# ADS8686S_BLOCK_B.net
KiCad netlist of a schematic drawn in Altium Designer
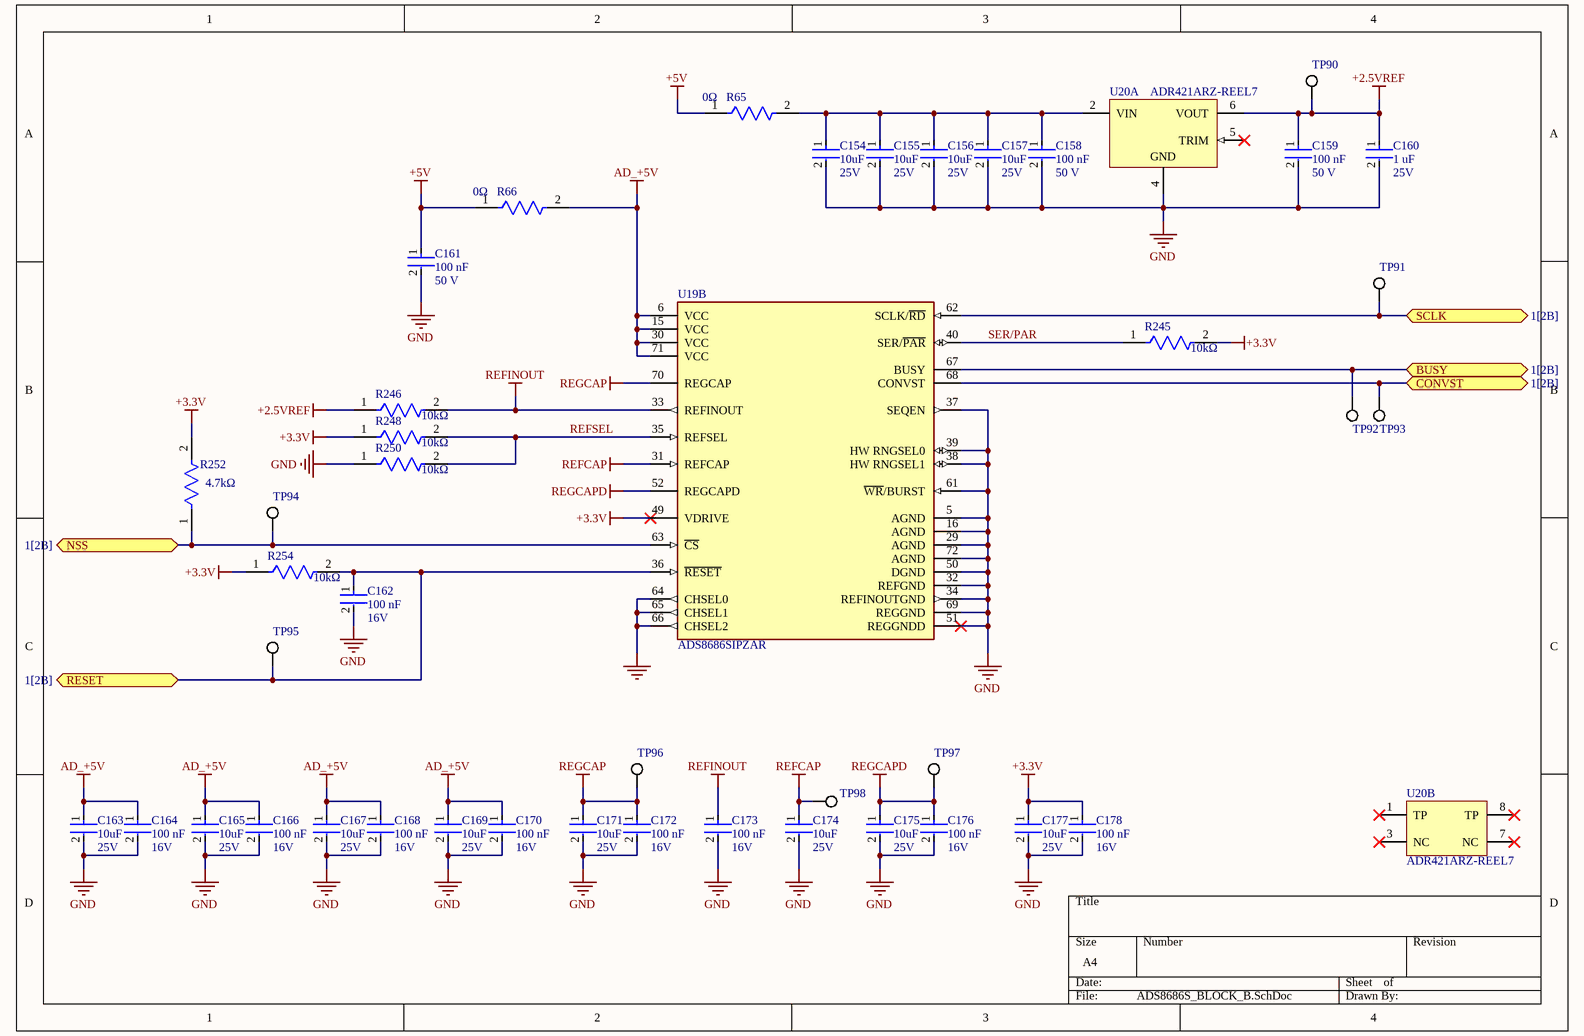
[diagram p0: ADS8686S_BLOCK_B.SchDoc]

(export (version "E")
  (design (tool "Eeschema 10.0.6"))
  (components
    (comp (ref "C154")
      (value "C1608X5R1E106M080AC")
      (footprint "FP-C1608-080-IPC_B")
      (description "CAP CER 10UF 25V X5R 0603")
      (fields
        (field (name "VOLTAGE RATING") "25V")
        (field (name "TOLERANCE") "20%")
        (field (name "CAPACITANCE") "10uF")
      )
      (libsource (lib "Altium Content Vault") (part "11868f565c42a9108669ba33697ecf6"))
    )
    (comp (ref "C155")
      (value "C1608X5R1E106M080AC")
      (footprint "FP-C1608-080-IPC_B")
      (description "CAP CER 10UF 25V X5R 0603")
      (fields
        (field (name "VOLTAGE RATING") "25V")
        (field (name "TOLERANCE") "20%")
        (field (name "CAPACITANCE") "10uF")
      )
      (libsource (lib "Altium Content Vault") (part "11868f565c42a9108669ba33697ecf6"))
    )
    (comp (ref "C156")
      (value "C1608X5R1E106M080AC")
      (footprint "FP-C1608-080-IPC_B")
      (description "CAP CER 10UF 25V X5R 0603")
      (fields
        (field (name "VOLTAGE RATING") "25V")
        (field (name "TOLERANCE") "20%")
        (field (name "CAPACITANCE") "10uF")
      )
      (libsource (lib "Altium Content Vault") (part "11868f565c42a9108669ba33697ecf6"))
    )
    (comp (ref "C157")
      (value "C1608X5R1E106M080AC")
      (footprint "FP-C1608-080-IPC_B")
      (description "CAP CER 10UF 25V X5R 0603")
      (fields
        (field (name "VOLTAGE RATING") "25V")
        (field (name "TOLERANCE") "20%")
        (field (name "CAPACITANCE") "10uF")
      )
      (libsource (lib "Altium Content Vault") (part "11868f565c42a9108669ba33697ecf6"))
    )
    (comp (ref "C158")
      (value "100 nF")
      (footprint "FP-C0603C-CF-IPC_B")
      (description "CAP CER 0.1UF 50V 20% X7R 0603")
      (fields
        (field (name "VOLTAGE RATING") "50 V")
        (field (name "MANUFACTURER PART NUMBER") "C0603C104M5RACTU")
        (field (name "MANUFACTURER") "KEMET")
      )
      (libsource (lib "Altium Content Vault") (part "b4654b650e69147ec39a6b967a45e02"))
    )
    (comp (ref "C159")
      (value "100 nF")
      (footprint "FP-C0603C-CF-IPC_B")
      (description "CAP CER 0.1UF 50V 20% X7R 0603")
      (fields
        (field (name "VOLTAGE RATING") "50 V")
        (field (name "MANUFACTURER PART NUMBER") "C0603C104M5RACTU")
        (field (name "MANUFACTURER") "KEMET")
      )
      (libsource (lib "Altium Content Vault") (part "b4654b650e69147ec39a6b967a45e02"))
    )
    (comp (ref "C160")
      (value "GCM188R71E105KA64D")
      (footprint "FP-GCM188-0_1-IPC_B")
      (fields
        (field (name "TOLERANCE") "10%")
        (field (name "CAPACITANCE") "1 uF")
        (field (name "VOLTAGE RATING") "25V")
        (field (name "VOLTAGE") "25V")
      )
      (libsource (lib "Altium Content Vault") (part "02cd4be3c70576c341d710602a673aa"))
    )
    (comp (ref "C161")
      (value "100 nF")
      (footprint "FP-C0603C-CF-IPC_B")
      (description "CAP CER 0.1UF 50V 20% X7R 0603")
      (fields
        (field (name "VOLTAGE RATING") "50 V")
        (field (name "MANUFACTURER PART NUMBER") "C0603C104M5RACTU")
        (field (name "MANUFACTURER") "KEMET")
      )
      (libsource (lib "Altium Content Vault") (part "b4654b650e69147ec39a6b967a45e02"))
    )
    (comp (ref "C162")
      (value "CL05B104KO5VPNC")
      (footprint "FP-CL752-IPC_B")
      (description "Cap Ceramic 100nF 16V X7R ±10% SMD 0402 +125°C Paper T/R")
      (fields
        (field (name "CAPACITANCE") "100 nF")
        (field (name "VOLTAGE RATING") "16V")
        (field (name "TOLERANCE") "10%")
      )
      (libsource (lib "Altium Content Vault") (part "b4654b650e69147ec39a6b967a45e02"))
    )
    (comp (ref "C163")
      (value "C1608X5R1E106M080AC")
      (footprint "FP-C1608-080-IPC_B")
      (description "CAP CER 10UF 25V X5R 0603")
      (fields
        (field (name "VOLTAGE RATING") "25V")
        (field (name "TOLERANCE") "20%")
        (field (name "CAPACITANCE") "10uF")
      )
      (libsource (lib "Altium Content Vault") (part "11868f565c42a9108669ba33697ecf6"))
    )
    (comp (ref "C164")
      (value "CL05B104KO5VPNC")
      (footprint "FP-CL752-IPC_B")
      (description "Cap Ceramic 100nF 16V X7R ±10% SMD 0402 +125°C Paper T/R")
      (fields
        (field (name "CAPACITANCE") "100 nF")
        (field (name "VOLTAGE RATING") "16V")
        (field (name "TOLERANCE") "10%")
      )
      (libsource (lib "Altium Content Vault") (part "b4654b650e69147ec39a6b967a45e02"))
    )
    (comp (ref "C165")
      (value "C1608X5R1E106M080AC")
      (footprint "FP-C1608-080-IPC_B")
      (description "CAP CER 10UF 25V X5R 0603")
      (fields
        (field (name "VOLTAGE RATING") "25V")
        (field (name "TOLERANCE") "20%")
        (field (name "CAPACITANCE") "10uF")
      )
      (libsource (lib "Altium Content Vault") (part "11868f565c42a9108669ba33697ecf6"))
    )
    (comp (ref "C166")
      (value "CL05B104KO5VPNC")
      (footprint "FP-CL752-IPC_B")
      (description "Cap Ceramic 100nF 16V X7R ±10% SMD 0402 +125°C Paper T/R")
      (fields
        (field (name "CAPACITANCE") "100 nF")
        (field (name "VOLTAGE RATING") "16V")
        (field (name "TOLERANCE") "10%")
      )
      (libsource (lib "Altium Content Vault") (part "b4654b650e69147ec39a6b967a45e02"))
    )
    (comp (ref "C167")
      (value "C1608X5R1E106M080AC")
      (footprint "FP-C1608-080-IPC_B")
      (description "CAP CER 10UF 25V X5R 0603")
      (fields
        (field (name "VOLTAGE RATING") "25V")
        (field (name "TOLERANCE") "20%")
        (field (name "CAPACITANCE") "10uF")
      )
      (libsource (lib "Altium Content Vault") (part "11868f565c42a9108669ba33697ecf6"))
    )
    (comp (ref "C168")
      (value "CL05B104KO5VPNC")
      (footprint "FP-CL752-IPC_B")
      (description "Cap Ceramic 100nF 16V X7R ±10% SMD 0402 +125°C Paper T/R")
      (fields
        (field (name "CAPACITANCE") "100 nF")
        (field (name "VOLTAGE RATING") "16V")
        (field (name "TOLERANCE") "10%")
      )
      (libsource (lib "Altium Content Vault") (part "b4654b650e69147ec39a6b967a45e02"))
    )
    (comp (ref "C169")
      (value "C1608X5R1E106M080AC")
      (footprint "FP-C1608-080-IPC_B")
      (description "CAP CER 10UF 25V X5R 0603")
      (fields
        (field (name "VOLTAGE RATING") "25V")
        (field (name "TOLERANCE") "20%")
        (field (name "CAPACITANCE") "10uF")
      )
      (libsource (lib "Altium Content Vault") (part "11868f565c42a9108669ba33697ecf6"))
    )
    (comp (ref "C170")
      (value "CL05B104KO5VPNC")
      (footprint "FP-CL752-IPC_B")
      (description "Cap Ceramic 100nF 16V X7R ±10% SMD 0402 +125°C Paper T/R")
      (fields
        (field (name "CAPACITANCE") "100 nF")
        (field (name "VOLTAGE RATING") "16V")
        (field (name "TOLERANCE") "10%")
      )
      (libsource (lib "Altium Content Vault") (part "b4654b650e69147ec39a6b967a45e02"))
    )
    (comp (ref "C171")
      (value "C1608X5R1E106M080AC")
      (footprint "FP-C1608-080-IPC_B")
      (description "CAP CER 10UF 25V X5R 0603")
      (fields
        (field (name "VOLTAGE RATING") "25V")
        (field (name "TOLERANCE") "20%")
        (field (name "CAPACITANCE") "10uF")
      )
      (libsource (lib "Altium Content Vault") (part "11868f565c42a9108669ba33697ecf6"))
    )
    (comp (ref "C172")
      (value "CL05B104KO5VPNC")
      (footprint "FP-CL752-IPC_B")
      (description "Cap Ceramic 100nF 16V X7R ±10% SMD 0402 +125°C Paper T/R")
      (fields
        (field (name "CAPACITANCE") "100 nF")
        (field (name "VOLTAGE RATING") "16V")
        (field (name "TOLERANCE") "10%")
      )
      (libsource (lib "Altium Content Vault") (part "b4654b650e69147ec39a6b967a45e02"))
    )
    (comp (ref "C173")
      (value "CL05B104KO5VPNC")
      (footprint "FP-CL752-IPC_B")
      (description "Cap Ceramic 100nF 16V X7R ±10% SMD 0402 +125°C Paper T/R")
      (fields
        (field (name "CAPACITANCE") "100 nF")
        (field (name "VOLTAGE RATING") "16V")
        (field (name "TOLERANCE") "10%")
      )
      (libsource (lib "Altium Content Vault") (part "b4654b650e69147ec39a6b967a45e02"))
    )
    (comp (ref "C174")
      (value "C1608X5R1E106M080AC")
      (footprint "FP-C1608-080-IPC_B")
      (description "CAP CER 10UF 25V X5R 0603")
      (fields
        (field (name "VOLTAGE RATING") "25V")
        (field (name "TOLERANCE") "20%")
        (field (name "CAPACITANCE") "10uF")
      )
      (libsource (lib "Altium Content Vault") (part "11868f565c42a9108669ba33697ecf6"))
    )
    (comp (ref "C175")
      (value "C1608X5R1E106M080AC")
      (footprint "FP-C1608-080-IPC_B")
      (description "CAP CER 10UF 25V X5R 0603")
      (fields
        (field (name "VOLTAGE RATING") "25V")
        (field (name "TOLERANCE") "20%")
        (field (name "CAPACITANCE") "10uF")
      )
      (libsource (lib "Altium Content Vault") (part "11868f565c42a9108669ba33697ecf6"))
    )
    (comp (ref "C176")
      (value "CL05B104KO5VPNC")
      (footprint "FP-CL752-IPC_B")
      (description "Cap Ceramic 100nF 16V X7R ±10% SMD 0402 +125°C Paper T/R")
      (fields
        (field (name "CAPACITANCE") "100 nF")
        (field (name "VOLTAGE RATING") "16V")
        (field (name "TOLERANCE") "10%")
      )
      (libsource (lib "Altium Content Vault") (part "b4654b650e69147ec39a6b967a45e02"))
    )
    (comp (ref "C177")
      (value "C1608X5R1E106M080AC")
      (footprint "FP-C1608-080-IPC_B")
      (description "CAP CER 10UF 25V X5R 0603")
      (fields
        (field (name "VOLTAGE RATING") "25V")
        (field (name "TOLERANCE") "20%")
        (field (name "CAPACITANCE") "10uF")
      )
      (libsource (lib "Altium Content Vault") (part "11868f565c42a9108669ba33697ecf6"))
    )
    (comp (ref "C178")
      (value "CL05B104KO5VPNC")
      (footprint "FP-CL752-IPC_B")
      (description "Cap Ceramic 100nF 16V X7R ±10% SMD 0402 +125°C Paper T/R")
      (fields
        (field (name "CAPACITANCE") "100 nF")
        (field (name "VOLTAGE RATING") "16V")
        (field (name "TOLERANCE") "10%")
      )
      (libsource (lib "Altium Content Vault") (part "b4654b650e69147ec39a6b967a45e02"))
    )
    (comp (ref "R65")
      (value "CRCW06030000Z0EAHP")
      (footprint "FP-CRCW0603-HPe3-IPC_B")
      (description "RES Thick Film, 0Ω, , 0.33W, , 0603")
      (fields (field (name "RESISTANCE") "0Ω"))
      (libsource (lib "Altium Content Vault") (part "1029c3af85768c4190bb7ad29bc67b5"))
    )
    (comp (ref "R66")
      (value "CRCW06030000Z0EAHP")
      (footprint "FP-CRCW0603-HPe3-IPC_B")
      (description "RES Thick Film, 0Ω, , 0.33W, , 0603")
      (fields (field (name "RESISTANCE") "0Ω"))
      (libsource (lib "Altium Content Vault") (part "1029c3af85768c4190bb7ad29bc67b5"))
    )
    (comp (ref "R245")
      (value "RC0603FR-0710KL")
      (footprint "FP-RC0603-0_55-IPC_B")
      (description "RES 10K OHM 1% 1/10W 0603")
      (fields (field (name "TOLERANCE") "1%") (field (name "RESISTANCE") "10kΩ"))
      (libsource (lib "Altium Content Vault") (part "1029c3af85768c4190bb7ad29bc67b5"))
    )
    (comp (ref "R246")
      (value "RC0603FR-0710KL")
      (footprint "FP-RC0603-0_55-IPC_B")
      (description "RES 10K OHM 1% 1/10W 0603")
      (fields (field (name "TOLERANCE") "1%") (field (name "RESISTANCE") "10kΩ"))
      (libsource (lib "Altium Content Vault") (part "1029c3af85768c4190bb7ad29bc67b5"))
    )
    (comp (ref "R248")
      (value "RC0603FR-0710KL")
      (footprint "FP-RC0603-0_55-IPC_B")
      (description "RES 10K OHM 1% 1/10W 0603")
      (fields (field (name "TOLERANCE") "1%") (field (name "RESISTANCE") "10kΩ"))
      (libsource (lib "Altium Content Vault") (part "1029c3af85768c4190bb7ad29bc67b5"))
    )
    (comp (ref "R250")
      (value "RC0603FR-0710KL")
      (footprint "FP-RC0603-0_55-IPC_B")
      (description "RES 10K OHM 1% 1/10W 0603")
      (fields (field (name "TOLERANCE") "1%") (field (name "RESISTANCE") "10kΩ"))
      (libsource (lib "Altium Content Vault") (part "1029c3af85768c4190bb7ad29bc67b5"))
    )
    (comp (ref "R252")
      (value "AC0603FR-074K7L")
      (footprint "FP-AC0603-IPC_B")
      (description "RES 4.7KΩ 1.00% 0.1W 0603")
      (fields (field (name "RESISTANCE") "4.7kΩ") (field (name "TOLERANCE") "1%"))
      (libsource (lib "Altium Content Vault") (part "1029c3af85768c4190bb7ad29bc67b5"))
    )
    (comp (ref "R254")
      (value "RC0603FR-0710KL")
      (footprint "FP-RC0603-0_55-IPC_B")
      (description "RES 10K OHM 1% 1/10W 0603")
      (fields (field (name "TOLERANCE") "1%") (field (name "RESISTANCE") "10kΩ"))
      (libsource (lib "Altium Content Vault") (part "1029c3af85768c4190bb7ad29bc67b5"))
    )
    (comp (ref "TP90")
      (value "5019")
      (footprint "KSTN-5019_V")
      (description "Test Point, 1 Position SMD, RoHS, Tape and Reel")
      (libsource (lib "Altium Content Vault") (part "TESTPOINT_WHITE"))
    )
    (comp (ref "TP91")
      (value "5019")
      (footprint "KSTN-5019_V")
      (description "Test Point, 1 Position SMD, RoHS, Tape and Reel")
      (libsource (lib "Altium Content Vault") (part "TESTPOINT_WHITE"))
    )
    (comp (ref "TP92")
      (value "5019")
      (footprint "KSTN-5019_V")
      (description "Test Point, 1 Position SMD, RoHS, Tape and Reel")
      (libsource (lib "Altium Content Vault") (part "TESTPOINT_WHITE"))
    )
    (comp (ref "TP93")
      (value "5019")
      (footprint "KSTN-5019_V")
      (description "Test Point, 1 Position SMD, RoHS, Tape and Reel")
      (libsource (lib "Altium Content Vault") (part "TESTPOINT_WHITE"))
    )
    (comp (ref "TP94")
      (value "5019")
      (footprint "KSTN-5019_V")
      (description "Test Point, 1 Position SMD, RoHS, Tape and Reel")
      (libsource (lib "Altium Content Vault") (part "TESTPOINT_WHITE"))
    )
    (comp (ref "TP95")
      (value "5019")
      (footprint "KSTN-5019_V")
      (description "Test Point, 1 Position SMD, RoHS, Tape and Reel")
      (libsource (lib "Altium Content Vault") (part "TESTPOINT_WHITE"))
    )
    (comp (ref "TP96")
      (value "5019")
      (footprint "KSTN-5019_V")
      (description "Test Point, 1 Position SMD, RoHS, Tape and Reel")
      (libsource (lib "Altium Content Vault") (part "TESTPOINT_WHITE"))
    )
    (comp (ref "TP97")
      (value "5019")
      (footprint "KSTN-5019_V")
      (description "Test Point, 1 Position SMD, RoHS, Tape and Reel")
      (libsource (lib "Altium Content Vault") (part "TESTPOINT_WHITE"))
    )
    (comp (ref "TP98")
      (value "5019")
      (footprint "KSTN-5019_V")
      (description "Test Point, 1 Position SMD, RoHS, Tape and Reel")
      (libsource (lib "Altium Content Vault") (part "TESTPOINT_WHITE"))
    )
    (comp (ref "U19")
      (value "ADS8686SIPZAR")
      (footprint "TI-RECOMMENDED")
      (fields (field (name "MANUFACTURER") "Texas Instruments"))
      (libsource (lib "ADS8686S") (part "ADS8686SIPZAR"))
    )
    (comp (ref "U20")
      (value "ADR421ARZ-REEL7")
      (footprint "ADI-R-8_M")
      (fields (field (name "MANUFACTURER") "Analog Devices"))
      (libsource (lib "Altium Content Vault") (part "ADI-ADR4XX-8"))
    )
  )
  (nets
    (net (code "1") (name "+2.5VREF") (class "Default")
      (node (ref "C159") (pin "1") (pinfunction "1_1") (pintype "passive"))
      (node (ref "C160") (pin "1") (pinfunction "1_1") (pintype "passive"))
      (node (ref "R246") (pin "1") (pinfunction "1_1") (pintype "passive"))
      (node (ref "TP90") (pin "1") (pinfunction "1_1") (pintype "passive"))
      (node (ref "U20") (pin "6") (pinfunction "VOUT_6") (pintype "power_in"))
    )
    (net (code "2") (name "+3.3V") (class "Default")
      (node (ref "C177") (pin "1") (pinfunction "1_1") (pintype "passive"))
      (node (ref "C178") (pin "1") (pinfunction "1_1") (pintype "passive"))
      (node (ref "R245") (pin "2") (pinfunction "2_2") (pintype "passive"))
      (node (ref "R248") (pin "1") (pinfunction "1_1") (pintype "passive"))
      (node (ref "R252") (pin "2") (pinfunction "2_2") (pintype "passive"))
      (node (ref "R254") (pin "1") (pinfunction "1_1") (pintype "passive"))
      (node (ref "U19") (pin "49") (pinfunction "VDRIVE_49") (pintype "power_in"))
    )
    (net (code "3") (name "+5V") (class "Default")
      (node (ref "C161") (pin "1") (pinfunction "1_1") (pintype "passive"))
      (node (ref "R65") (pin "1") (pinfunction "1_1") (pintype "passive"))
      (node (ref "R66") (pin "1") (pinfunction "1_1") (pintype "passive"))
    )
    (net (code "4") (name "/BUSY") (class "Default")
      (node (ref "TP92") (pin "1") (pinfunction "1_1") (pintype "passive"))
      (node (ref "U19") (pin "67") (pinfunction "BUSY_67") (pintype "passive"))
    )
    (net (code "5") (name "/CONVST") (class "Default")
      (node (ref "TP93") (pin "1") (pinfunction "1_1") (pintype "passive"))
      (node (ref "U19") (pin "68") (pinfunction "CONVST_68") (pintype "passive"))
    )
    (net (code "6") (name "/NSS") (class "Default")
      (node (ref "R252") (pin "1") (pinfunction "1_1") (pintype "passive"))
      (node (ref "TP94") (pin "1") (pinfunction "1_1") (pintype "passive"))
      (node (ref "U19") (pin "63") (pinfunction "~{CS}_63") (pintype "input"))
    )
    (net (code "7") (name "/REFSEL") (class "Default")
      (node (ref "R248") (pin "2") (pinfunction "2_2") (pintype "passive"))
      (node (ref "R250") (pin "2") (pinfunction "2_2") (pintype "passive"))
      (node (ref "U19") (pin "35") (pinfunction "REFSEL_35") (pintype "input"))
    )
    (net (code "8") (name "/RESET") (class "Default")
      (node (ref "C162") (pin "1") (pinfunction "1_1") (pintype "passive"))
      (node (ref "R254") (pin "2") (pinfunction "2_2") (pintype "passive"))
      (node (ref "TP95") (pin "1") (pinfunction "1_1") (pintype "passive"))
      (node (ref "U19") (pin "36") (pinfunction "~{RESET}_36") (pintype "input"))
    )
    (net (code "9") (name "/SCLK") (class "Default")
      (node (ref "TP91") (pin "1") (pinfunction "1_1") (pintype "passive"))
      (node (ref "U19") (pin "62") (pinfunction "SCLK/~{RD}_62") (pintype "input"))
    )
    (net (code "10") (name "/SER{slash}PAR") (class "Default")
      (node (ref "R245") (pin "1") (pinfunction "1_1") (pintype "passive"))
      (node (ref "U19") (pin "40") (pinfunction "SER/~{PAR}_40") (pintype "bidirectional"))
    )
    (net (code "11") (name "AD_+5V") (class "Default")
      (node (ref "C163") (pin "1") (pinfunction "1_1") (pintype "passive"))
      (node (ref "C164") (pin "1") (pinfunction "1_1") (pintype "passive"))
      (node (ref "C165") (pin "1") (pinfunction "1_1") (pintype "passive"))
      (node (ref "C166") (pin "1") (pinfunction "1_1") (pintype "passive"))
      (node (ref "C167") (pin "1") (pinfunction "1_1") (pintype "passive"))
      (node (ref "C168") (pin "1") (pinfunction "1_1") (pintype "passive"))
      (node (ref "C169") (pin "1") (pinfunction "1_1") (pintype "passive"))
      (node (ref "C170") (pin "1") (pinfunction "1_1") (pintype "passive"))
      (node (ref "R66") (pin "2") (pinfunction "2_2") (pintype "passive"))
      (node (ref "U19") (pin "15") (pinfunction "VCC_15") (pintype "power_in"))
      (node (ref "U19") (pin "30") (pinfunction "VCC_30") (pintype "power_in"))
      (node (ref "U19") (pin "6") (pinfunction "VCC_6") (pintype "power_in"))
      (node (ref "U19") (pin "71") (pinfunction "VCC_71") (pintype "power_in"))
    )
    (net (code "12") (name "GND") (class "Default")
      (node (ref "C154") (pin "2") (pinfunction "2_2") (pintype "passive"))
      (node (ref "C155") (pin "2") (pinfunction "2_2") (pintype "passive"))
      (node (ref "C156") (pin "2") (pinfunction "2_2") (pintype "passive"))
      (node (ref "C157") (pin "2") (pinfunction "2_2") (pintype "passive"))
      (node (ref "C158") (pin "2") (pinfunction "2_2") (pintype "passive"))
      (node (ref "C159") (pin "2") (pinfunction "2_2") (pintype "passive"))
      (node (ref "C160") (pin "2") (pinfunction "2_2") (pintype "passive"))
      (node (ref "C161") (pin "2") (pinfunction "2_2") (pintype "passive"))
      (node (ref "C162") (pin "2") (pinfunction "2_2") (pintype "passive"))
      (node (ref "C163") (pin "2") (pinfunction "2_2") (pintype "passive"))
      (node (ref "C164") (pin "2") (pinfunction "2_2") (pintype "passive"))
      (node (ref "C165") (pin "2") (pinfunction "2_2") (pintype "passive"))
      (node (ref "C166") (pin "2") (pinfunction "2_2") (pintype "passive"))
      (node (ref "C167") (pin "2") (pinfunction "2_2") (pintype "passive"))
      (node (ref "C168") (pin "2") (pinfunction "2_2") (pintype "passive"))
      (node (ref "C169") (pin "2") (pinfunction "2_2") (pintype "passive"))
      (node (ref "C170") (pin "2") (pinfunction "2_2") (pintype "passive"))
      (node (ref "C171") (pin "2") (pinfunction "2_2") (pintype "passive"))
      (node (ref "C172") (pin "2") (pinfunction "2_2") (pintype "passive"))
      (node (ref "C173") (pin "2") (pinfunction "2_2") (pintype "passive"))
      (node (ref "C174") (pin "2") (pinfunction "2_2") (pintype "passive"))
      (node (ref "C175") (pin "2") (pinfunction "2_2") (pintype "passive"))
      (node (ref "C176") (pin "2") (pinfunction "2_2") (pintype "passive"))
      (node (ref "C177") (pin "2") (pinfunction "2_2") (pintype "passive"))
      (node (ref "C178") (pin "2") (pinfunction "2_2") (pintype "passive"))
      (node (ref "R250") (pin "1") (pinfunction "1_1") (pintype "passive"))
      (node (ref "U19") (pin "16") (pinfunction "AGND_16") (pintype "power_in"))
      (node (ref "U19") (pin "29") (pinfunction "AGND_29") (pintype "power_in"))
      (node (ref "U19") (pin "32") (pinfunction "REFGND_32") (pintype "power_in"))
      (node (ref "U19") (pin "34") (pinfunction "REFINOUTGND_34") (pintype "output"))
      (node (ref "U19") (pin "37") (pinfunction "SEQEN_37") (pintype "output"))
      (node (ref "U19") (pin "38") (pinfunction "HW_RNGSEL1_38") (pintype "bidirectional"))
      (node (ref "U19") (pin "39") (pinfunction "HW_RNGSEL0_39") (pintype "bidirectional"))
      (node (ref "U19") (pin "5") (pinfunction "AGND_5") (pintype "power_in"))
      (node (ref "U19") (pin "50") (pinfunction "DGND_50") (pintype "power_in"))
      (node (ref "U19") (pin "51") (pinfunction "REGGNDD_51") (pintype "power_in"))
      (node (ref "U19") (pin "61") (pinfunction "~{WR}/BURST_61") (pintype "input"))
      (node (ref "U19") (pin "64") (pinfunction "CHSEL0_64") (pintype "output"))
      (node (ref "U19") (pin "65") (pinfunction "CHSEL1_65") (pintype "output"))
      (node (ref "U19") (pin "66") (pinfunction "CHSEL2_66") (pintype "output"))
      (node (ref "U19") (pin "69") (pinfunction "REGGND_69") (pintype "power_in"))
      (node (ref "U19") (pin "72") (pinfunction "AGND_72") (pintype "power_in"))
      (node (ref "U20") (pin "4") (pinfunction "GND_4") (pintype "power_in"))
    )
    (net (code "13") (name "Net-(U20A-VIN)") (class "Default")
      (node (ref "C154") (pin "1") (pinfunction "1_1") (pintype "passive"))
      (node (ref "C155") (pin "1") (pinfunction "1_1") (pintype "passive"))
      (node (ref "C156") (pin "1") (pinfunction "1_1") (pintype "passive"))
      (node (ref "C157") (pin "1") (pinfunction "1_1") (pintype "passive"))
      (node (ref "C158") (pin "1") (pinfunction "1_1") (pintype "passive"))
      (node (ref "R65") (pin "2") (pinfunction "2_2") (pintype "passive"))
      (node (ref "U20") (pin "2") (pinfunction "VIN_2") (pintype "power_in"))
    )
    (net (code "14") (name "REFCAP") (class "Default")
      (node (ref "C174") (pin "1") (pinfunction "1_1") (pintype "passive"))
      (node (ref "TP98") (pin "1") (pinfunction "1_1") (pintype "passive"))
      (node (ref "U19") (pin "31") (pinfunction "REFCAP_31") (pintype "input"))
    )
    (net (code "15") (name "REFINOUT") (class "Default")
      (node (ref "C173") (pin "1") (pinfunction "1_1") (pintype "passive"))
      (node (ref "R246") (pin "2") (pinfunction "2_2") (pintype "passive"))
      (node (ref "U19") (pin "33") (pinfunction "REFINOUT_33") (pintype "output"))
    )
    (net (code "16") (name "REGCAP") (class "Default")
      (node (ref "C171") (pin "1") (pinfunction "1_1") (pintype "passive"))
      (node (ref "C172") (pin "1") (pinfunction "1_1") (pintype "passive"))
      (node (ref "TP96") (pin "1") (pinfunction "1_1") (pintype "passive"))
      (node (ref "U19") (pin "70") (pinfunction "REGCAP_70") (pintype "power_in"))
    )
    (net (code "17") (name "REGCAPD") (class "Default")
      (node (ref "C175") (pin "1") (pinfunction "1_1") (pintype "passive"))
      (node (ref "C176") (pin "1") (pinfunction "1_1") (pintype "passive"))
      (node (ref "TP97") (pin "1") (pinfunction "1_1") (pintype "passive"))
      (node (ref "U19") (pin "52") (pinfunction "REGCAPD_52") (pintype "power_in"))
    )
    (net (code "18") (name "unconnected-(U20A-TRIM-Pad5)") (class "Default")
      (node (ref "U20") (pin "5") (pinfunction "TRIM_5") (pintype "input+no_connect"))
    )
    (net (code "19") (name "unconnected-(U20B-NC-Pad3)") (class "Default")
      (node (ref "U20") (pin "3") (pinfunction "NC_3") (pintype "passive+no_connect"))
    )
    (net (code "20") (name "unconnected-(U20B-NC-Pad7)") (class "Default")
      (node (ref "U20") (pin "7") (pinfunction "NC_7") (pintype "passive+no_connect"))
    )
    (net (code "21") (name "unconnected-(U20B-TP-Pad1)") (class "Default")
      (node (ref "U20") (pin "1") (pinfunction "TP_1") (pintype "passive+no_connect"))
    )
    (net (code "22") (name "unconnected-(U20B-TP-Pad8)") (class "Default")
      (node (ref "U20") (pin "8") (pinfunction "TP_8") (pintype "passive+no_connect"))
    )
  )
)
